# Flodar_Board.net
KiCad netlist of a schematic drawn in EAGLE
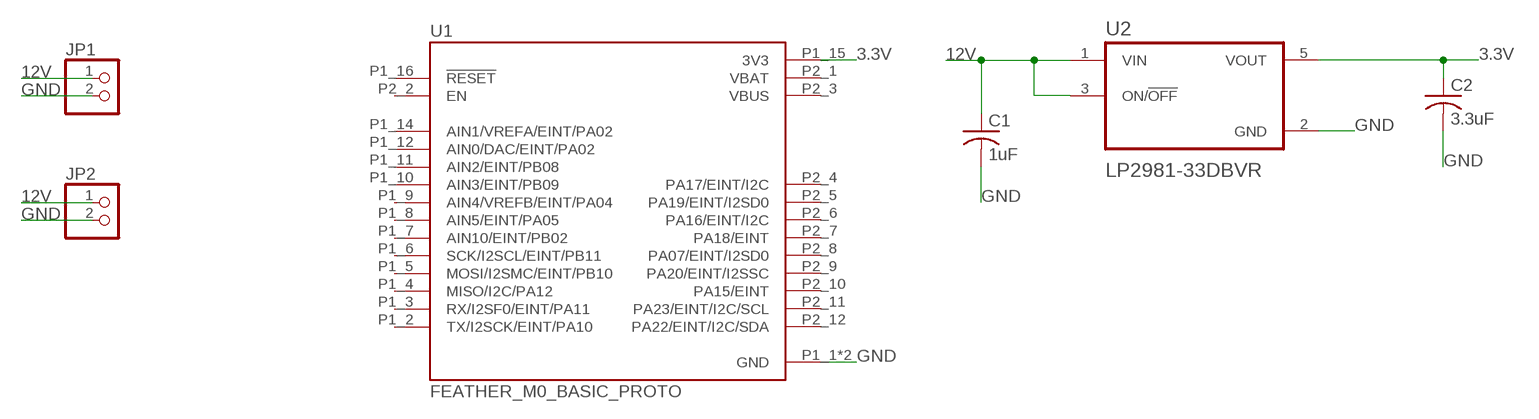
[diagram p0: schematic, sheet 1]

(export (version "E")
  (design (tool "Eeschema 10.0.6"))
  (components
    (comp (ref "C1")
      (value "1uF")
      (footprint "eagle-import:C1206")
      (libsource (lib "eagle-import") (part "C-USC1206"))
    )
    (comp (ref "C2")
      (value "3.3uF")
      (footprint "eagle-import:C1206")
      (libsource (lib "eagle-import") (part "C-USC1206"))
    )
    (comp (ref "JP1")
      (value "PINHD-1X2")
      (footprint "eagle-import:1X02")
      (libsource (lib "eagle-import") (part "PINHD-1X2"))
    )
    (comp (ref "JP2")
      (value "PINHD-1X2")
      (footprint "eagle-import:1X02")
      (libsource (lib "eagle-import") (part "PINHD-1X2"))
    )
    (comp (ref "U1")
      (value "FEATHER_M0_BASIC_PROTO")
      (footprint "eagle-import:MODULE_FEATHER_M0_BASIC_PROTO")
      (fields (field (name "MF") "Adafruit Industries") (field (name "MP") "Feather M0 Basic Proto"))
      (libsource (lib "eagle-import") (part "FEATHER_M0_BASIC_PROTO"))
    )
    (comp (ref "U2")
      (value "LP2981-33DBVR")
      (footprint "eagle-import:SOT95P280X145-5N")
      (fields (field (name "MF") "Texas Instruments") (field (name "MP") "LP2981-50DBVR"))
      (libsource (lib "eagle-import") (part "LP2981-50DBVR"))
    )
  )
  (nets
    (net (code "1") (name "/3.3V") (class "Default")
      (node (ref "C2") (pin "1") (pinfunction "1_1") (pintype "passive"))
      (node (ref "U1") (pin "P1_15") (pinfunction "3V3_P1_15") (pintype "power_in"))
      (node (ref "U2") (pin "5") (pinfunction "VOUT_5") (pintype "output"))
    )
    (net (code "2") (name "/12V") (class "Default")
      (node (ref "C1") (pin "1") (pinfunction "1_1") (pintype "passive"))
      (node (ref "JP1") (pin "1") (pinfunction "1_1") (pintype "passive"))
      (node (ref "JP2") (pin "1") (pinfunction "1_1") (pintype "passive"))
      (node (ref "U2") (pin "1") (pinfunction "VIN_1") (pintype "input"))
      (node (ref "U2") (pin "3") (pinfunction "ON/~{OFF}_3") (pintype "bidirectional"))
    )
    (net (code "3") (name "/GND") (class "Default")
      (node (ref "C1") (pin "2") (pinfunction "2_2") (pintype "passive"))
      (node (ref "C2") (pin "2") (pinfunction "2_2") (pintype "passive"))
      (node (ref "JP1") (pin "2") (pinfunction "2_2") (pintype "passive"))
      (node (ref "JP2") (pin "2") (pinfunction "2_2") (pintype "passive"))
      (node (ref "U1") (pin "P1_1") (pinfunction "GND_P1_1") (pintype "power_in"))
      (node (ref "U1") (pin "P1_13") (pinfunction "GND_P1_13") (pintype "power_in"))
      (node (ref "U2") (pin "2") (pinfunction "GND_2") (pintype "power_in"))
    )
    (net (code "4") (name "/VBAT") (class "Default")
      (node (ref "U1") (pin "P2_1") (pinfunction "VBAT_P2_1") (pintype "power_in"))
    )
    (net (code "5") (name "/VBUS") (class "Default")
      (node (ref "U1") (pin "P2_3") (pinfunction "VBUS_P2_3") (pintype "power_in"))
    )
    (net (code "6") (name "unconnected-(U1-AIN0{slash}DAC{slash}EINT{slash}PA02-PadP1_12)") (class "Default")
      (node (ref "U1") (pin "P1_12") (pinfunction "AIN0/DAC/EINT/PA02_P1_12") (pintype "bidirectional"))
    )
    (net (code "7") (name "unconnected-(U1-AIN1{slash}VREFA{slash}EINT{slash}PA02-PadP1_14)") (class "Default")
      (node (ref "U1") (pin "P1_14") (pinfunction "AIN1/VREFA/EINT/PA02_P1_14") (pintype "bidirectional"))
    )
    (net (code "8") (name "unconnected-(U1-AIN2{slash}EINT{slash}PB08-PadP1_11)") (class "Default")
      (node (ref "U1") (pin "P1_11") (pinfunction "AIN2/EINT/PB08_P1_11") (pintype "bidirectional"))
    )
    (net (code "9") (name "unconnected-(U1-AIN3{slash}EINT{slash}PB09-PadP1_10)") (class "Default")
      (node (ref "U1") (pin "P1_10") (pinfunction "AIN3/EINT/PB09_P1_10") (pintype "bidirectional"))
    )
    (net (code "10") (name "unconnected-(U1-AIN4{slash}VREFB{slash}EINT{slash}PA04-PadP1_9)") (class "Default")
      (node (ref "U1") (pin "P1_9") (pinfunction "AIN4/VREFB/EINT/PA04_P1_9") (pintype "bidirectional"))
    )
    (net (code "11") (name "unconnected-(U1-AIN5{slash}EINT{slash}PA05-PadP1_8)") (class "Default")
      (node (ref "U1") (pin "P1_8") (pinfunction "AIN5/EINT/PA05_P1_8") (pintype "bidirectional"))
    )
    (net (code "12") (name "unconnected-(U1-AIN10{slash}EINT{slash}PB02-PadP1_7)") (class "Default")
      (node (ref "U1") (pin "P1_7") (pinfunction "AIN10/EINT/PB02_P1_7") (pintype "bidirectional"))
    )
    (net (code "13") (name "unconnected-(U1-EN-PadP2_2)") (class "Default")
      (node (ref "U1") (pin "P2_2") (pinfunction "EN_P2_2") (pintype "input"))
    )
    (net (code "14") (name "unconnected-(U1-MISO{slash}I2C{slash}PA12-PadP1_4)") (class "Default")
      (node (ref "U1") (pin "P1_4") (pinfunction "MISO/I2C/PA12_P1_4") (pintype "bidirectional"))
    )
    (net (code "15") (name "unconnected-(U1-MOSI{slash}I2SMC{slash}EINT{slash}PB10-PadP1_5)") (class "Default")
      (node (ref "U1") (pin "P1_5") (pinfunction "MOSI/I2SMC/EINT/PB10_P1_5") (pintype "bidirectional"))
    )
    (net (code "16") (name "unconnected-(U1-PA07{slash}EINT{slash}I2SD0-PadP2_8)") (class "Default")
      (node (ref "U1") (pin "P2_8") (pinfunction "PA07/EINT/I2SD0_P2_8") (pintype "bidirectional"))
    )
    (net (code "17") (name "unconnected-(U1-PA15{slash}EINT-PadP2_10)") (class "Default")
      (node (ref "U1") (pin "P2_10") (pinfunction "PA15/EINT_P2_10") (pintype "bidirectional"))
    )
    (net (code "18") (name "unconnected-(U1-PA16{slash}EINT{slash}I2C-PadP2_6)") (class "Default")
      (node (ref "U1") (pin "P2_6") (pinfunction "PA16/EINT/I2C_P2_6") (pintype "bidirectional"))
    )
    (net (code "19") (name "unconnected-(U1-PA17{slash}EINT{slash}I2C-PadP2_4)") (class "Default")
      (node (ref "U1") (pin "P2_4") (pinfunction "PA17/EINT/I2C_P2_4") (pintype "bidirectional"))
    )
    (net (code "20") (name "unconnected-(U1-PA18{slash}EINT-PadP2_7)") (class "Default")
      (node (ref "U1") (pin "P2_7") (pinfunction "PA18/EINT_P2_7") (pintype "bidirectional"))
    )
    (net (code "21") (name "unconnected-(U1-PA19{slash}EINT{slash}I2SD0-PadP2_5)") (class "Default")
      (node (ref "U1") (pin "P2_5") (pinfunction "PA19/EINT/I2SD0_P2_5") (pintype "bidirectional"))
    )
    (net (code "22") (name "unconnected-(U1-PA20{slash}EINT{slash}I2SSC-PadP2_9)") (class "Default")
      (node (ref "U1") (pin "P2_9") (pinfunction "PA20/EINT/I2SSC_P2_9") (pintype "bidirectional"))
    )
    (net (code "23") (name "unconnected-(U1-PA22{slash}EINT{slash}I2C{slash}SDA-PadP2_12)") (class "Default")
      (node (ref "U1") (pin "P2_12") (pinfunction "PA22/EINT/I2C/SDA_P2_12") (pintype "bidirectional"))
    )
    (net (code "24") (name "unconnected-(U1-PA23{slash}EINT{slash}I2C{slash}SCL-PadP2_11)") (class "Default")
      (node (ref "U1") (pin "P2_11") (pinfunction "PA23/EINT/I2C/SCL_P2_11") (pintype "bidirectional"))
    )
    (net (code "25") (name "unconnected-(U1-RX{slash}I2SF0{slash}EINT{slash}PA11-PadP1_3)") (class "Default")
      (node (ref "U1") (pin "P1_3") (pinfunction "RX/I2SF0/EINT/PA11_P1_3") (pintype "bidirectional"))
    )
    (net (code "26") (name "unconnected-(U1-SCK{slash}I2SCL{slash}EINT{slash}PB11-PadP1_6)") (class "Default")
      (node (ref "U1") (pin "P1_6") (pinfunction "SCK/I2SCL/EINT/PB11_P1_6") (pintype "bidirectional"))
    )
    (net (code "27") (name "unconnected-(U1-TX{slash}I2SCK{slash}EINT{slash}PA10-PadP1_2)") (class "Default")
      (node (ref "U1") (pin "P1_2") (pinfunction "TX/I2SCK/EINT/PA10_P1_2") (pintype "bidirectional"))
    )
    (net (code "28") (name "unconnected-(U1-~{RESET}-PadP1_16)") (class "Default")
      (node (ref "U1") (pin "P1_16") (pinfunction "~{RESET}_P1_16") (pintype "input"))
    )
  )
)
